# Power_suply.net
KiCad netlist of a schematic drawn in Altium Designer
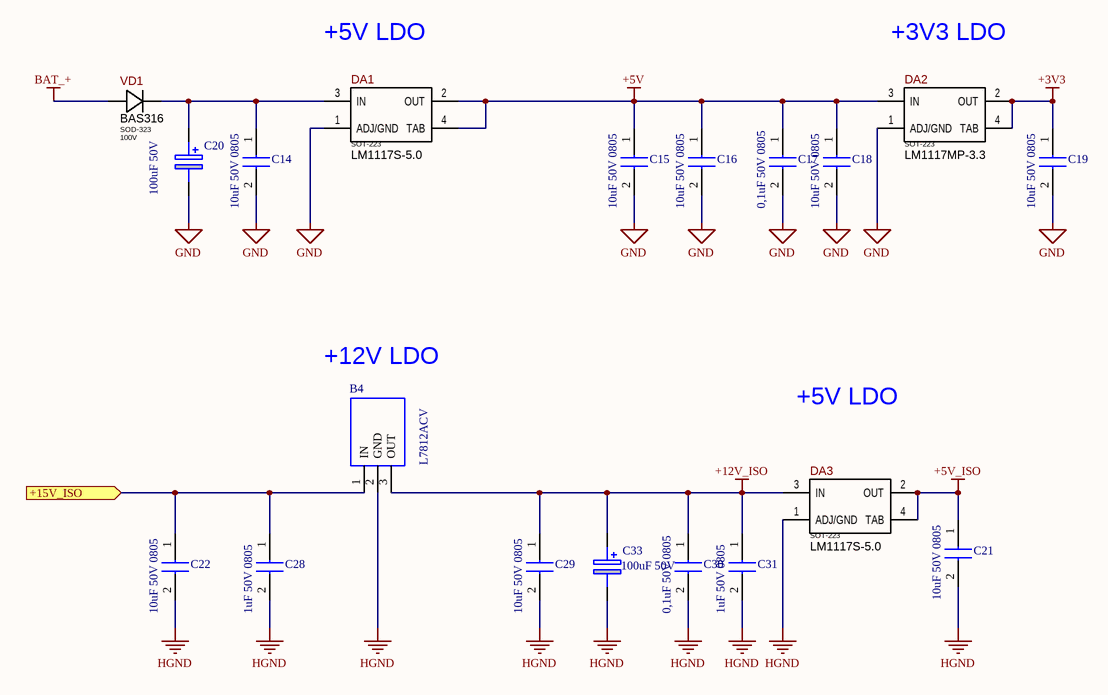
[diagram p0: Power_suply.SchDoc]

(export (version "E")
  (design (tool "Eeschema 10.0.6"))
  (components
    (comp (ref "B4")
      (value "L7812ACV")
      (footprint "TO270P460X1020X2008-3P")
      (fields (field (name "MOUSER PART NUMBER") "511-L7812ACV"))
      (libsource (lib "L7812ACV") (part "L7812ACV"))
    )
    (comp (ref "C14")
      (value "10uF 50V 0805")
      (footprint "SamacSys:CAPC2012X90N")
      (description "Capacitor")
      (libsource (lib "*") (part "MCMT21N470F250CT"))
    )
    (comp (ref "C15")
      (value "10uF 50V 0805")
      (footprint "SamacSys:CAPC2012X90N")
      (description "Capacitor")
      (libsource (lib "*") (part "MCMT21N470F250CT"))
    )
    (comp (ref "C16")
      (value "10uF 50V 0805")
      (footprint "SamacSys:CAPC2012X90N")
      (description "Capacitor")
      (libsource (lib "*") (part "MCMT21N470F250CT"))
    )
    (comp (ref "C17")
      (value "0,1uF 50V 0805")
      (footprint "SamacSys:CAPC2012X90N")
      (description "Capacitor")
      (libsource (lib "*") (part "MCMT21N470F250CT"))
    )
    (comp (ref "C18")
      (value "10uF 50V 0805")
      (footprint "SamacSys:CAPC2012X90N")
      (description "Capacitor")
      (libsource (lib "*") (part "MCMT21N470F250CT"))
    )
    (comp (ref "C19")
      (value "10uF 50V 0805")
      (footprint "SamacSys:CAPC2012X90N")
      (description "Capacitor")
      (libsource (lib "*") (part "MCMT21N470F250CT"))
    )
    (comp (ref "C20")
      (value "100uF 50V")
      (footprint "CAPPRD500W60D870H1200")
      (description "Aluminum Electrolytic Capacitors - Radial Leaded 100uF 50V 20% Radial")
      (fields
        (field (name "MANUFACTURER_PART_NUMBER") "MAL203690109E3")
        (field (name "MOUSER PART NUMBER") "594-2222-036-90109")
      )
      (libsource (lib "MAL203690109E3") (part "MAL203690109E3"))
    )
    (comp (ref "C21")
      (value "10uF 50V 0805")
      (footprint "SamacSys:CAPC2012X90N")
      (description "Capacitor")
      (libsource (lib "*") (part "MCMT21N470F250CT"))
    )
    (comp (ref "C22")
      (value "10uF 50V 0805")
      (footprint "SamacSys:CAPC2012X90N")
      (description "Capacitor")
      (libsource (lib "*") (part "MCMT21N470F250CT"))
    )
    (comp (ref "C28")
      (value "1uF 50V 0805")
      (footprint "SamacSys:CAPC2012X90N")
      (description "Capacitor")
      (libsource (lib "*") (part "MCMT21N470F250CT"))
    )
    (comp (ref "C29")
      (value "10uF 50V 0805")
      (footprint "SamacSys:CAPC2012X90N")
      (description "Capacitor")
      (libsource (lib "*") (part "MCMT21N470F250CT"))
    )
    (comp (ref "C30")
      (value "0,1uF 50V 0805")
      (footprint "SamacSys:CAPC2012X90N")
      (description "Capacitor")
      (libsource (lib "*") (part "MCMT21N470F250CT"))
    )
    (comp (ref "C31")
      (value "1uF 50V 0805")
      (footprint "SamacSys:CAPC2012X90N")
      (description "Capacitor")
      (libsource (lib "*") (part "MCMT21N470F250CT"))
    )
    (comp (ref "C33")
      (value "100uF 50V")
      (footprint "CAPPRD500W60D870H1200")
      (description "Aluminum Electrolytic Capacitors - Radial Leaded 100uF 50V 20% Radial")
      (fields
        (field (name "MANUFACTURER_PART_NUMBER") "MAL203690109E3")
        (field (name "MOUSER PART NUMBER") "594-2222-036-90109")
      )
      (libsource (lib "MAL203690109E3") (part "MAL203690109E3"))
    )
    (comp (ref "DA1")
      (value "~")
      (footprint "SOT-223")
      (description "Linear Voltage Regulator IC 1 Output 800mA SOT-223")
      (fields (field (name "PACKAGE") "SOT-223") (field (name "PART NUMBER") "LM1117S-5.0"))
      (libsource (lib "AjaxLibrary") (part "LM1117MP-xx"))
    )
    (comp (ref "DA2")
      (value "~")
      (footprint "SOT-223")
      (description "Linear Voltage Regulator IC 1 Output 800mA SOT-223")
      (fields
        (field (name "PACKAGE") "SOT-223")
        (field (name "PART NUMBER") "LM1117MP-3.3")
        (field (name "MANUFACTURER") "Texas Instruments")
      )
      (libsource (lib "AjaxLibrary") (part "LM1117MP-xx"))
    )
    (comp (ref "DA3")
      (value "~")
      (footprint "SOT-223")
      (description "Linear Voltage Regulator IC 1 Output 800mA SOT-223")
      (fields (field (name "PACKAGE") "SOT-223") (field (name "PART NUMBER") "LM1117S-5.0"))
      (libsource (lib "AjaxLibrary") (part "LM1117MP-xx"))
    )
    (comp (ref "VD1")
      (value "BAS316")
      (footprint "SOD-323_MED")
      (description "Diode Standard 100V 250mA, SOD-323/SC-76")
      (fields
        (field (name "PART NUMBER") "BAS316")
        (field (name "PACKAGE") "SOD-323")
        (field (name "VOLTAGE") "100V")
        (field (name "MANUFACTURER") "Nexperia USA Inc.")
      )
      (libsource (lib "AjaxLibrary") (part "Diode-General"))
    )
  )
  (nets
    (net (code "1") (name "+3V3") (class "Default")
      (node (ref "C19") (pin "1") (pinfunction "1_1") (pintype "passive"))
      (node (ref "DA2") (pin "2") (pinfunction "OUT_2") (pintype "passive"))
      (node (ref "DA2") (pin "4") (pinfunction "TAB_4") (pintype "passive"))
    )
    (net (code "2") (name "+5V") (class "Default")
      (node (ref "C15") (pin "1") (pinfunction "1_1") (pintype "passive"))
      (node (ref "C16") (pin "1") (pinfunction "1_1") (pintype "passive"))
      (node (ref "C17") (pin "1") (pinfunction "1_1") (pintype "passive"))
      (node (ref "C18") (pin "1") (pinfunction "1_1") (pintype "passive"))
      (node (ref "DA1") (pin "2") (pinfunction "OUT_2") (pintype "passive"))
      (node (ref "DA1") (pin "4") (pinfunction "TAB_4") (pintype "passive"))
      (node (ref "DA2") (pin "3") (pinfunction "IN_3") (pintype "passive"))
    )
    (net (code "3") (name "+5V_ISO") (class "Default")
      (node (ref "C21") (pin "1") (pinfunction "1_1") (pintype "passive"))
      (node (ref "DA3") (pin "2") (pinfunction "OUT_2") (pintype "passive"))
      (node (ref "DA3") (pin "4") (pinfunction "TAB_4") (pintype "passive"))
    )
    (net (code "4") (name "+12V_ISO") (class "Default")
      (node (ref "B4") (pin "3") (pinfunction "OUT_3") (pintype "passive"))
      (node (ref "C29") (pin "1") (pinfunction "1_1") (pintype "passive"))
      (node (ref "C30") (pin "1") (pinfunction "1_1") (pintype "passive"))
      (node (ref "C31") (pin "1") (pinfunction "1_1") (pintype "passive"))
      (node (ref "C33") (pin "1") (pinfunction "+_1") (pintype "passive"))
      (node (ref "DA3") (pin "3") (pinfunction "IN_3") (pintype "passive"))
    )
    (net (code "5") (name "/+15V_ISO") (class "Default")
      (node (ref "B4") (pin "1") (pinfunction "IN_1") (pintype "passive"))
      (node (ref "C22") (pin "1") (pinfunction "1_1") (pintype "passive"))
      (node (ref "C28") (pin "1") (pinfunction "1_1") (pintype "passive"))
    )
    (net (code "6") (name "BAT_+") (class "Default") (node (ref "VD1") (pin "AN") (pintype "passive")))
    (net (code "7") (name "GND") (class "Default")
      (node (ref "C14") (pin "2") (pinfunction "2_2") (pintype "passive"))
      (node (ref "C15") (pin "2") (pinfunction "2_2") (pintype "passive"))
      (node (ref "C16") (pin "2") (pinfunction "2_2") (pintype "passive"))
      (node (ref "C17") (pin "2") (pinfunction "2_2") (pintype "passive"))
      (node (ref "C18") (pin "2") (pinfunction "2_2") (pintype "passive"))
      (node (ref "C19") (pin "2") (pinfunction "2_2") (pintype "passive"))
      (node (ref "C20") (pin "2") (pinfunction "-_2") (pintype "passive"))
      (node (ref "DA1") (pin "1") (pinfunction "ADJ/GND_1") (pintype "passive"))
      (node (ref "DA2") (pin "1") (pinfunction "ADJ/GND_1") (pintype "passive"))
    )
    (net (code "8") (name "HGND") (class "Default")
      (node (ref "B4") (pin "2") (pinfunction "GND_2") (pintype "power_in"))
      (node (ref "C21") (pin "2") (pinfunction "2_2") (pintype "passive"))
      (node (ref "C22") (pin "2") (pinfunction "2_2") (pintype "passive"))
      (node (ref "C28") (pin "2") (pinfunction "2_2") (pintype "passive"))
      (node (ref "C29") (pin "2") (pinfunction "2_2") (pintype "passive"))
      (node (ref "C30") (pin "2") (pinfunction "2_2") (pintype "passive"))
      (node (ref "C31") (pin "2") (pinfunction "2_2") (pintype "passive"))
      (node (ref "C33") (pin "2") (pinfunction "-_2") (pintype "passive"))
      (node (ref "DA3") (pin "1") (pinfunction "ADJ/GND_1") (pintype "passive"))
    )
    (net (code "9") (name "Net-(C20-+)") (class "Default")
      (node (ref "C14") (pin "1") (pinfunction "1_1") (pintype "passive"))
      (node (ref "C20") (pin "1") (pinfunction "+_1") (pintype "passive"))
      (node (ref "DA1") (pin "3") (pinfunction "IN_3") (pintype "passive"))
      (node (ref "VD1") (pin "CA") (pintype "passive"))
    )
  )
)
